# G-103P-20190808.net
KiCad netlist of a schematic drawn in Altium Designer
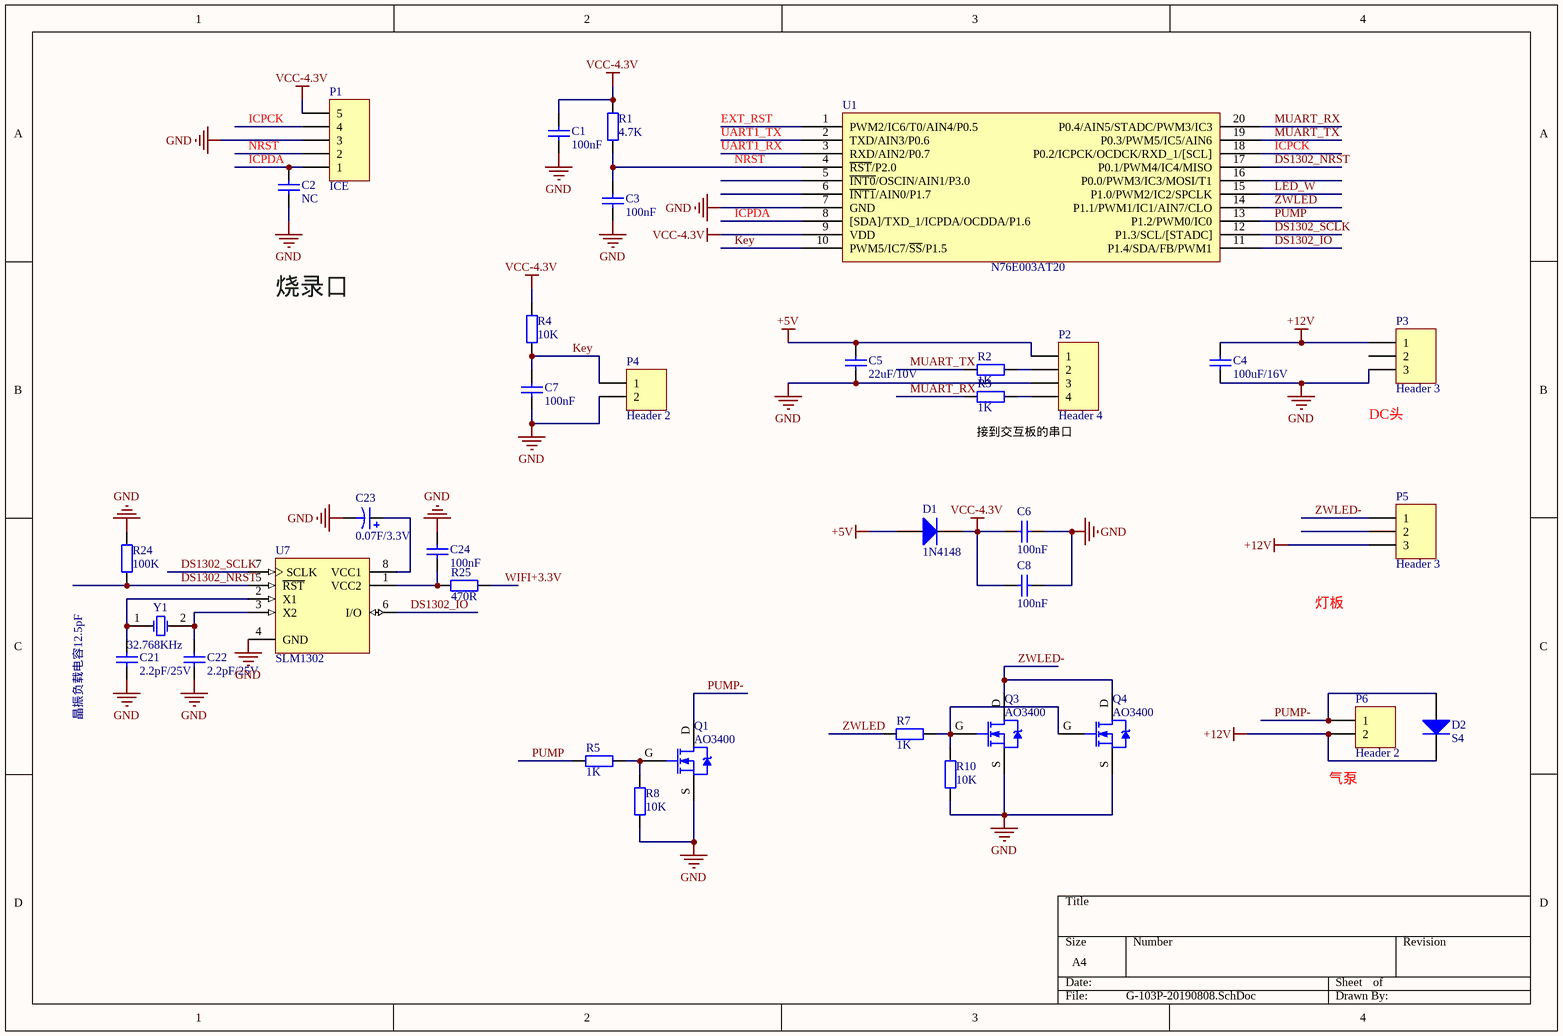
[diagram p0: G-103P-20190808.SchDoc]

(export (version "E")
  (design (tool "Eeschema 10.0.6"))
  (components
    (comp (ref "C1")
      (value "100nF")
      (footprint "SMD-0603")
      (description "Capacitor")
      (fields (field (name "Comment") "Cap") (field (name "PUBLISHER") "Altium Limited"))
      (libsource (lib "Miscellaneous Devices") (part "Cap"))
    )
    (comp (ref "C2")
      (value "NC")
      (footprint "SMD-0603")
      (description "Capacitor")
      (fields (field (name "PUBLISHER") "Altium Limited"))
      (libsource (lib "Miscellaneous Devices") (part "Cap"))
    )
    (comp (ref "C3")
      (value "100nF")
      (footprint "SMD-0603")
      (description "Capacitor")
      (fields (field (name "Comment") "Cap") (field (name "PUBLISHER") "Altium Limited"))
      (libsource (lib "Miscellaneous Devices") (part "Cap"))
    )
    (comp (ref "C4")
      (value "100uF/16V")
      (footprint "CAPR6.3W")
      (description "Capacitor")
      (fields (field (name "PUBLISHER") "Altium Limited"))
      (libsource (lib "Miscellaneous Devices") (part "Cap"))
    )
    (comp (ref "C5")
      (value "22uF/10V")
      (footprint "SMD-0603")
      (description "Capacitor")
      (fields (field (name "PUBLISHER") "Altium Limited"))
      (libsource (lib "Miscellaneous Devices") (part "Cap"))
    )
    (comp (ref "C6")
      (value "100nF")
      (footprint "SMD-0603")
      (description "Capacitor")
      (fields (field (name "PUBLISHER") "Altium Limited"))
      (libsource (lib "Miscellaneous Devices") (part "Cap"))
    )
    (comp (ref "C7")
      (value "100nF")
      (footprint "SMD-0603")
      (description "Capacitor")
      (fields (field (name "PUBLISHER") "Altium Limited"))
      (libsource (lib "Miscellaneous Devices") (part "Cap"))
    )
    (comp (ref "C8")
      (value "100nF")
      (footprint "SMD-0603")
      (description "Capacitor")
      (fields (field (name "PUBLISHER") "Altium Limited"))
      (libsource (lib "Miscellaneous Devices") (part "Cap"))
    )
    (comp (ref "C21")
      (value "2.2pF/25V")
      (footprint "SMD-0603M")
      (description "Capacitor")
      (fields (field (name "PUBLISHER") "Altium Limited"))
      (libsource (lib "Miscellaneous Devices") (part "Cap"))
    )
    (comp (ref "C22")
      (value "2.2pF/25V")
      (footprint "SMD-0603M")
      (description "Capacitor")
      (fields (field (name "PUBLISHER") "Altium Limited"))
      (libsource (lib "Miscellaneous Devices") (part "Cap"))
    )
    (comp (ref "C23")
      (value "0.07F/3.3V")
      (footprint "CS-ME-414-TA")
      (description "Polarized Capacitor (Radial)")
      (fields (field (name "PUBLISHER") "Altium Limited"))
      (libsource (lib "Miscellaneous Devices") (part "Cap Pol1"))
    )
    (comp (ref "C24")
      (value "100nF")
      (footprint "SMD-0603M")
      (description "Capacitor")
      (fields (field (name "PUBLISHER") "Altium Limited"))
      (libsource (lib "Miscellaneous Devices") (part "Cap"))
    )
    (comp (ref "D1")
      (value "1N4148")
      (footprint "SOD123")
      (description "1 Amp General Purpose Rectifier")
      (fields (field (name "PUBLISHER") "Altium Limited"))
      (libsource (lib "Miscellaneous Devices") (part "Diode 1N4007"))
    )
    (comp (ref "D2")
      (value "S4")
      (footprint "SOD123")
      (description "1 Amp General Purpose Rectifier")
      (fields (field (name "PUBLISHER") "Altium Limited"))
      (libsource (lib "Miscellaneous Devices") (part "Diode 1N4007"))
    )
    (comp (ref "P1")
      (value "ICE")
      (footprint "HDR1X5")
      (description "Header, 5-Pin")
      (fields (field (name "PUBLISHER") "Altium Limited"))
      (libsource (lib "Miscellaneous Connectors") (part "Header 5"))
    )
    (comp (ref "P2")
      (value "Header 4")
      (footprint "PH-2.0-4P")
      (description "Header, 4-Pin")
      (fields (field (name "PUBLISHER") "Altium Limited"))
      (libsource (lib "Miscellaneous Connectors") (part "Header 4"))
    )
    (comp (ref "P3")
      (value "Header 3")
      (footprint "DC-MU")
      (description "Header, 3-Pin")
      (fields (field (name "PUBLISHER") "Altium Limited"))
      (libsource (lib "Miscellaneous Connectors") (part "Header 3"))
    )
    (comp (ref "P4")
      (value "Header 2")
      (footprint "KYE-F")
      (description "Header, 2-Pin")
      (fields (field (name "PUBLISHER") "Altium Limited"))
      (libsource (lib "Miscellaneous Connectors") (part "Header 2"))
    )
    (comp (ref "P5")
      (value "Header 3")
      (footprint "2.54-3PW")
      (description "Header, 3-Pin")
      (fields (field (name "PUBLISHER") "Altium Limited"))
      (libsource (lib "Miscellaneous Connectors") (part "Header 3"))
    )
    (comp (ref "P6")
      (value "Header 2")
      (footprint "2.54-2PW")
      (description "Header, 2-Pin")
      (fields (field (name "PUBLISHER") "Altium Limited"))
      (libsource (lib "Miscellaneous Connectors") (part "Header 2"))
    )
    (comp (ref "Q1")
      (value "AO3400")
      (footprint "SOT-23E3")
      (description "N-Channel Power MOSFET")
      (fields (field (name "PUBLISHER") "Altium Limited"))
      (libsource (lib "TouchLED") (part "NMOS-2"))
    )
    (comp (ref "Q3")
      (value "AO3400")
      (footprint "SOT-23E3")
      (description "N-Channel Power MOSFET")
      (fields (field (name "PUBLISHER") "Altium Limited"))
      (libsource (lib "TouchLED") (part "NMOS-2"))
    )
    (comp (ref "Q4")
      (value "AO3400")
      (footprint "SOT-23E3")
      (description "N-Channel Power MOSFET")
      (fields (field (name "PUBLISHER") "Altium Limited"))
      (libsource (lib "TouchLED") (part "NMOS-2"))
    )
    (comp (ref "R1")
      (value "4.7K")
      (footprint "SMD-0603")
      (description "Resistor")
      (fields (field (name "Comment") "Res2") (field (name "PUBLISHER") "Altium Limited"))
      (libsource (lib "") (part "Res2_1"))
    )
    (comp (ref "R2")
      (value "1K")
      (footprint "SMD-0603")
      (description "Resistor")
      (fields (field (name "PUBLISHER") "Altium Limited"))
      (libsource (lib "Miscellaneous Devices") (part "Res2"))
    )
    (comp (ref "R3")
      (value "1K")
      (footprint "SMD-0603")
      (description "Resistor")
      (fields (field (name "PUBLISHER") "Altium Limited"))
      (libsource (lib "Miscellaneous Devices") (part "Res2"))
    )
    (comp (ref "R4")
      (value "10K")
      (footprint "SMD-0603")
      (description "Resistor")
      (fields (field (name "PUBLISHER") "Altium Limited"))
      (libsource (lib "") (part "Res2_1"))
    )
    (comp (ref "R5")
      (value "1K")
      (footprint "SMD-0603")
      (description "Resistor")
      (fields (field (name "PUBLISHER") "Altium Limited"))
      (libsource (lib "Miscellaneous Devices") (part "Res2"))
    )
    (comp (ref "R7")
      (value "1K")
      (footprint "SMD-0603")
      (description "Resistor")
      (fields (field (name "PUBLISHER") "Altium Limited"))
      (libsource (lib "Miscellaneous Devices") (part "Res2"))
    )
    (comp (ref "R8")
      (value "10K")
      (footprint "SMD-0603")
      (description "Resistor")
      (fields (field (name "PUBLISHER") "Altium Limited"))
      (libsource (lib "") (part "Res2_1"))
    )
    (comp (ref "R10")
      (value "10K")
      (footprint "SMD-0603")
      (description "Resistor")
      (fields (field (name "PUBLISHER") "Altium Limited"))
      (libsource (lib "") (part "Res2_1"))
    )
    (comp (ref "R24")
      (value "100K")
      (footprint "SMD-0603M")
      (description "Resistor")
      (fields (field (name "PUBLISHER") "Altium Limited"))
      (libsource (lib "") (part "Res2_1"))
    )
    (comp (ref "R25")
      (value "470R")
      (footprint "SMD-0603M")
      (description "Resistor")
      (fields (field (name "PUBLISHER") "Altium Limited"))
      (libsource (lib "Miscellaneous Devices") (part "Res2"))
    )
    (comp (ref "U1")
      (value "N76E003AT20")
      (footprint "TSSOP-20")
      (libsource (lib "AQ405_Power") (part "N76E003AT20"))
    )
    (comp (ref "U7")
      (value "SLM1302")
      (footprint "SOP8")
      (description "Trickle Charge Timekeeping Chip")
      (fields (field (name "PUBLISHER") "Altium Limited"))
      (libsource (lib "Dallas Peripheral Real Time Clock") (part "DS1302Z"))
    )
    (comp (ref "Y1")
      (value "32.768KHz")
      (footprint "BCY-W2/D3.1")
      (description "Crystal Oscillator")
      (fields (field (name "PUBLISHER") "Altium Limited"))
      (libsource (lib "Miscellaneous Devices") (part "XTAL"))
    )
  )
  (nets
    (net (code "1") (name "+5V") (class "Default")
      (node (ref "C5") (pin "2") (pinfunction "2_2") (pintype "passive"))
      (node (ref "D1") (pin "1") (pinfunction "A_1") (pintype "passive"))
      (node (ref "P2") (pin "1") (pinfunction "1_1") (pintype "passive"))
    )
    (net (code "2") (name "+12V") (class "Default")
      (node (ref "C4") (pin "2") (pinfunction "2_2") (pintype "passive"))
      (node (ref "D2") (pin "2") (pinfunction "K_2") (pintype "passive"))
      (node (ref "P3") (pin "1") (pinfunction "1_1") (pintype "passive"))
      (node (ref "P5") (pin "3") (pinfunction "3_3") (pintype "passive"))
      (node (ref "P6") (pin "2") (pinfunction "2_2") (pintype "passive"))
    )
    (net (code "3") (name "/DS1302_IO") (class "Default")
      (node (ref "U1") (pin "11") (pinfunction "P1.4/SDA/FB/PWM1_11") (pintype "passive"))
      (node (ref "U7") (pin "6") (pinfunction "I/O_6") (pintype "bidirectional"))
    )
    (net (code "4") (name "/DS1302_NRST") (class "Default")
      (node (ref "R24") (pin "2") (pinfunction "2_2") (pintype "passive"))
      (node (ref "U1") (pin "17") (pinfunction "P0.1/PWM4/IC4/MISO_17") (pintype "passive"))
      (node (ref "U7") (pin "5") (pinfunction "~{RST}_5") (pintype "input"))
    )
    (net (code "5") (name "/DS1302_SCLK") (class "Default")
      (node (ref "U1") (pin "12") (pinfunction "P1.3/SCL/[STADC]_12") (pintype "passive"))
      (node (ref "U7") (pin "7") (pinfunction "SCLK_7") (pintype "input"))
    )
    (net (code "6") (name "/EXT_RST") (class "Default")
      (node (ref "U1") (pin "1") (pinfunction "PWM2/IC6/T0/AIN4/P0.5_1") (pintype "passive"))
    )
    (net (code "7") (name "/ICPCK") (class "Default")
      (node (ref "P1") (pin "4") (pinfunction "4_4") (pintype "passive"))
      (node (ref "U1") (pin "18") (pinfunction "P0.2/ICPCK/OCDCK/RXD_1/[SCL]_18") (pintype "passive"))
    )
    (net (code "8") (name "/ICPDA") (class "Default")
      (node (ref "C2") (pin "1") (pinfunction "1_1") (pintype "passive"))
      (node (ref "P1") (pin "1") (pinfunction "1_1") (pintype "passive"))
      (node (ref "U1") (pin "8") (pinfunction "[SDA]/TXD_1/ICPDA/OCDDA/P1.6_8") (pintype "passive"))
    )
    (net (code "9") (name "/Key") (class "Default")
      (node (ref "C7") (pin "1") (pinfunction "1_1") (pintype "passive"))
      (node (ref "P4") (pin "1") (pinfunction "1_1") (pintype "passive"))
      (node (ref "R4") (pin "2") (pinfunction "2_2") (pintype "passive"))
      (node (ref "U1") (pin "10") (pinfunction "PWM5/IC7/~{SS}/P1.5_10") (pintype "passive"))
    )
    (net (code "10") (name "/LED_W") (class "Default")
      (node (ref "U1") (pin "15") (pinfunction "P1.0/PWM2/IC2/SPCLK_15") (pintype "passive"))
    )
    (net (code "11") (name "/MUART_RX") (class "Default")
      (node (ref "R3") (pin "2") (pinfunction "2_2") (pintype "passive"))
      (node (ref "U1") (pin "20") (pinfunction "P0.4/AIN5/STADC/PWM3/IC3_20") (pintype "passive"))
    )
    (net (code "12") (name "/MUART_TX") (class "Default")
      (node (ref "R2") (pin "2") (pinfunction "2_2") (pintype "passive"))
      (node (ref "U1") (pin "19") (pinfunction "P0.3/PWM5/IC5/AIN6_19") (pintype "passive"))
    )
    (net (code "13") (name "/NRST") (class "Default")
      (node (ref "C3") (pin "2") (pinfunction "2_2") (pintype "passive"))
      (node (ref "P1") (pin "2") (pinfunction "2_2") (pintype "passive"))
      (node (ref "R1") (pin "2") (pinfunction "2_2") (pintype "passive"))
      (node (ref "U1") (pin "4") (pinfunction "~{RST}/P2.0_4") (pintype "passive"))
    )
    (net (code "14") (name "/PUMP") (class "Default")
      (node (ref "R5") (pin "2") (pinfunction "2_2") (pintype "passive"))
      (node (ref "U1") (pin "13") (pinfunction "P1.2/PWM0/IC0_13") (pintype "passive"))
    )
    (net (code "15") (name "/PUMP-") (class "Default")
      (node (ref "D2") (pin "1") (pinfunction "A_1") (pintype "passive"))
      (node (ref "P6") (pin "1") (pinfunction "1_1") (pintype "passive"))
      (node (ref "Q1") (pin "D") (pinfunction "D_D") (pintype "passive"))
    )
    (net (code "16") (name "/UART1_RX") (class "Default")
      (node (ref "U1") (pin "3") (pinfunction "RXD/AIN2/P0.7_3") (pintype "passive"))
    )
    (net (code "17") (name "/UART1_TX") (class "Default")
      (node (ref "U1") (pin "2") (pinfunction "TXD/AIN3/P0.6_2") (pintype "passive"))
    )
    (net (code "18") (name "/WIFI+3.3V") (class "Default")
      (node (ref "R25") (pin "1") (pinfunction "1_1") (pintype "passive"))
    )
    (net (code "19") (name "/ZWLED") (class "Default")
      (node (ref "R7") (pin "2") (pinfunction "2_2") (pintype "passive"))
      (node (ref "U1") (pin "14") (pinfunction "P1.1/PWM1/IC1/AIN7/CLO_14") (pintype "passive"))
    )
    (net (code "20") (name "/ZWLED-") (class "Default")
      (node (ref "P5") (pin "1") (pinfunction "1_1") (pintype "passive"))
      (node (ref "Q3") (pin "D") (pinfunction "D_D") (pintype "passive"))
      (node (ref "Q4") (pin "D") (pinfunction "D_D") (pintype "passive"))
    )
    (net (code "21") (name "GND") (class "Default")
      (node (ref "C1") (pin "1") (pinfunction "1_1") (pintype "passive"))
      (node (ref "C2") (pin "2") (pinfunction "2_2") (pintype "passive"))
      (node (ref "C21") (pin "1") (pinfunction "1_1") (pintype "passive"))
      (node (ref "C22") (pin "1") (pinfunction "1_1") (pintype "passive"))
      (node (ref "C23") (pin "2") (pinfunction "2_2") (pintype "passive"))
      (node (ref "C24") (pin "2") (pinfunction "2_2") (pintype "passive"))
      (node (ref "C3") (pin "1") (pinfunction "1_1") (pintype "passive"))
      (node (ref "C4") (pin "1") (pinfunction "1_1") (pintype "passive"))
      (node (ref "C5") (pin "1") (pinfunction "1_1") (pintype "passive"))
      (node (ref "C6") (pin "1") (pinfunction "1_1") (pintype "passive"))
      (node (ref "C7") (pin "2") (pinfunction "2_2") (pintype "passive"))
      (node (ref "C8") (pin "1") (pinfunction "1_1") (pintype "passive"))
      (node (ref "P1") (pin "3") (pinfunction "3_3") (pintype "passive"))
      (node (ref "P2") (pin "3") (pinfunction "3_3") (pintype "passive"))
      (node (ref "P3") (pin "3") (pinfunction "3_3") (pintype "passive"))
      (node (ref "P4") (pin "2") (pinfunction "2_2") (pintype "passive"))
      (node (ref "Q1") (pin "S") (pinfunction "S_S") (pintype "passive"))
      (node (ref "Q3") (pin "S") (pinfunction "S_S") (pintype "passive"))
      (node (ref "Q4") (pin "S") (pinfunction "S_S") (pintype "passive"))
      (node (ref "R10") (pin "2") (pinfunction "2_2") (pintype "passive"))
      (node (ref "R24") (pin "1") (pinfunction "1_1") (pintype "passive"))
      (node (ref "R8") (pin "2") (pinfunction "2_2") (pintype "passive"))
      (node (ref "U1") (pin "7") (pinfunction "GND_7") (pintype "passive"))
      (node (ref "U7") (pin "4") (pinfunction "GND_4") (pintype "power_in"))
    )
    (net (code "22") (name "Net-(P2-Pad2)") (class "Default")
      (node (ref "P2") (pin "2") (pinfunction "2_2") (pintype "passive"))
      (node (ref "R2") (pin "1") (pinfunction "1_1") (pintype "passive"))
    )
    (net (code "23") (name "Net-(P2-Pad4)") (class "Default")
      (node (ref "P2") (pin "4") (pinfunction "4_4") (pintype "passive"))
      (node (ref "R3") (pin "1") (pinfunction "1_1") (pintype "passive"))
    )
    (net (code "24") (name "Net-(Q1-PadG)") (class "Default")
      (node (ref "Q1") (pin "G") (pinfunction "G_G") (pintype "passive"))
      (node (ref "R5") (pin "1") (pinfunction "1_1") (pintype "passive"))
      (node (ref "R8") (pin "1") (pinfunction "1_1") (pintype "passive"))
    )
    (net (code "25") (name "Net-(Q3-PadG)") (class "Default")
      (node (ref "Q3") (pin "G") (pinfunction "G_G") (pintype "passive"))
      (node (ref "Q4") (pin "G") (pinfunction "G_G") (pintype "passive"))
      (node (ref "R10") (pin "1") (pinfunction "1_1") (pintype "passive"))
      (node (ref "R7") (pin "1") (pinfunction "1_1") (pintype "passive"))
    )
    (net (code "26") (name "Net-(U7-VCC1)") (class "Default")
      (node (ref "C23") (pin "1") (pinfunction "1_1") (pintype "passive"))
      (node (ref "U7") (pin "8") (pinfunction "VCC1_8") (pintype "power_in"))
    )
    (net (code "27") (name "Net-(U7-VCC2)") (class "Default")
      (node (ref "C24") (pin "1") (pinfunction "1_1") (pintype "passive"))
      (node (ref "R25") (pin "2") (pinfunction "2_2") (pintype "passive"))
      (node (ref "U7") (pin "1") (pinfunction "VCC2_1") (pintype "power_in"))
    )
    (net (code "28") (name "Net-(U7-X1)") (class "Default")
      (node (ref "C21") (pin "2") (pinfunction "2_2") (pintype "passive"))
      (node (ref "U7") (pin "2") (pinfunction "X1_2") (pintype "input"))
      (node (ref "Y1") (pin "1") (pinfunction "OSC1_1") (pintype "passive"))
    )
    (net (code "29") (name "Net-(U7-X2)") (class "Default")
      (node (ref "C22") (pin "2") (pinfunction "2_2") (pintype "passive"))
      (node (ref "U7") (pin "3") (pinfunction "X2_3") (pintype "input"))
      (node (ref "Y1") (pin "2") (pinfunction "OSC2_2") (pintype "passive"))
    )
    (net (code "30") (name "VCC-4.3V") (class "Default")
      (node (ref "C1") (pin "2") (pinfunction "2_2") (pintype "passive"))
      (node (ref "C6") (pin "2") (pinfunction "2_2") (pintype "passive"))
      (node (ref "C8") (pin "2") (pinfunction "2_2") (pintype "passive"))
      (node (ref "D1") (pin "2") (pinfunction "K_2") (pintype "passive"))
      (node (ref "P1") (pin "5") (pinfunction "5_5") (pintype "passive"))
      (node (ref "R1") (pin "1") (pinfunction "1_1") (pintype "passive"))
      (node (ref "R4") (pin "1") (pinfunction "1_1") (pintype "passive"))
      (node (ref "U1") (pin "9") (pinfunction "VDD_9") (pintype "passive"))
    )
    (net (code "31") (name "unconnected-(P3-Pad2)") (class "Default")
      (node (ref "P3") (pin "2") (pinfunction "2_2") (pintype "passive"))
    )
    (net (code "32") (name "unconnected-(P5-Pad2)") (class "Default")
      (node (ref "P5") (pin "2") (pinfunction "2_2") (pintype "passive"))
    )
    (net (code "33") (name "unconnected-(U1-P0.0{slash}PWM3{slash}IC3{slash}MOSI{slash}T1-Pad16)") (class "Default")
      (node (ref "U1") (pin "16") (pinfunction "P0.0/PWM3/IC3/MOSI/T1_16") (pintype "passive"))
    )
    (net (code "34") (name "unconnected-(U1-~{INT0}{slash}OSCIN{slash}AIN1{slash}P3.0-Pad5)") (class "Default")
      (node (ref "U1") (pin "5") (pinfunction "~{INT0}/OSCIN/AIN1/P3.0_5") (pintype "passive"))
    )
    (net (code "35") (name "unconnected-(U1-~{INT1}{slash}AIN0{slash}P1.7-Pad6)") (class "Default")
      (node (ref "U1") (pin "6") (pinfunction "~{INT1}/AIN0/P1.7_6") (pintype "passive"))
    )
  )
)
